# Adafruit_NeoPixel_Ring_16_B.net
KiCad netlist of a schematic drawn in EAGLE
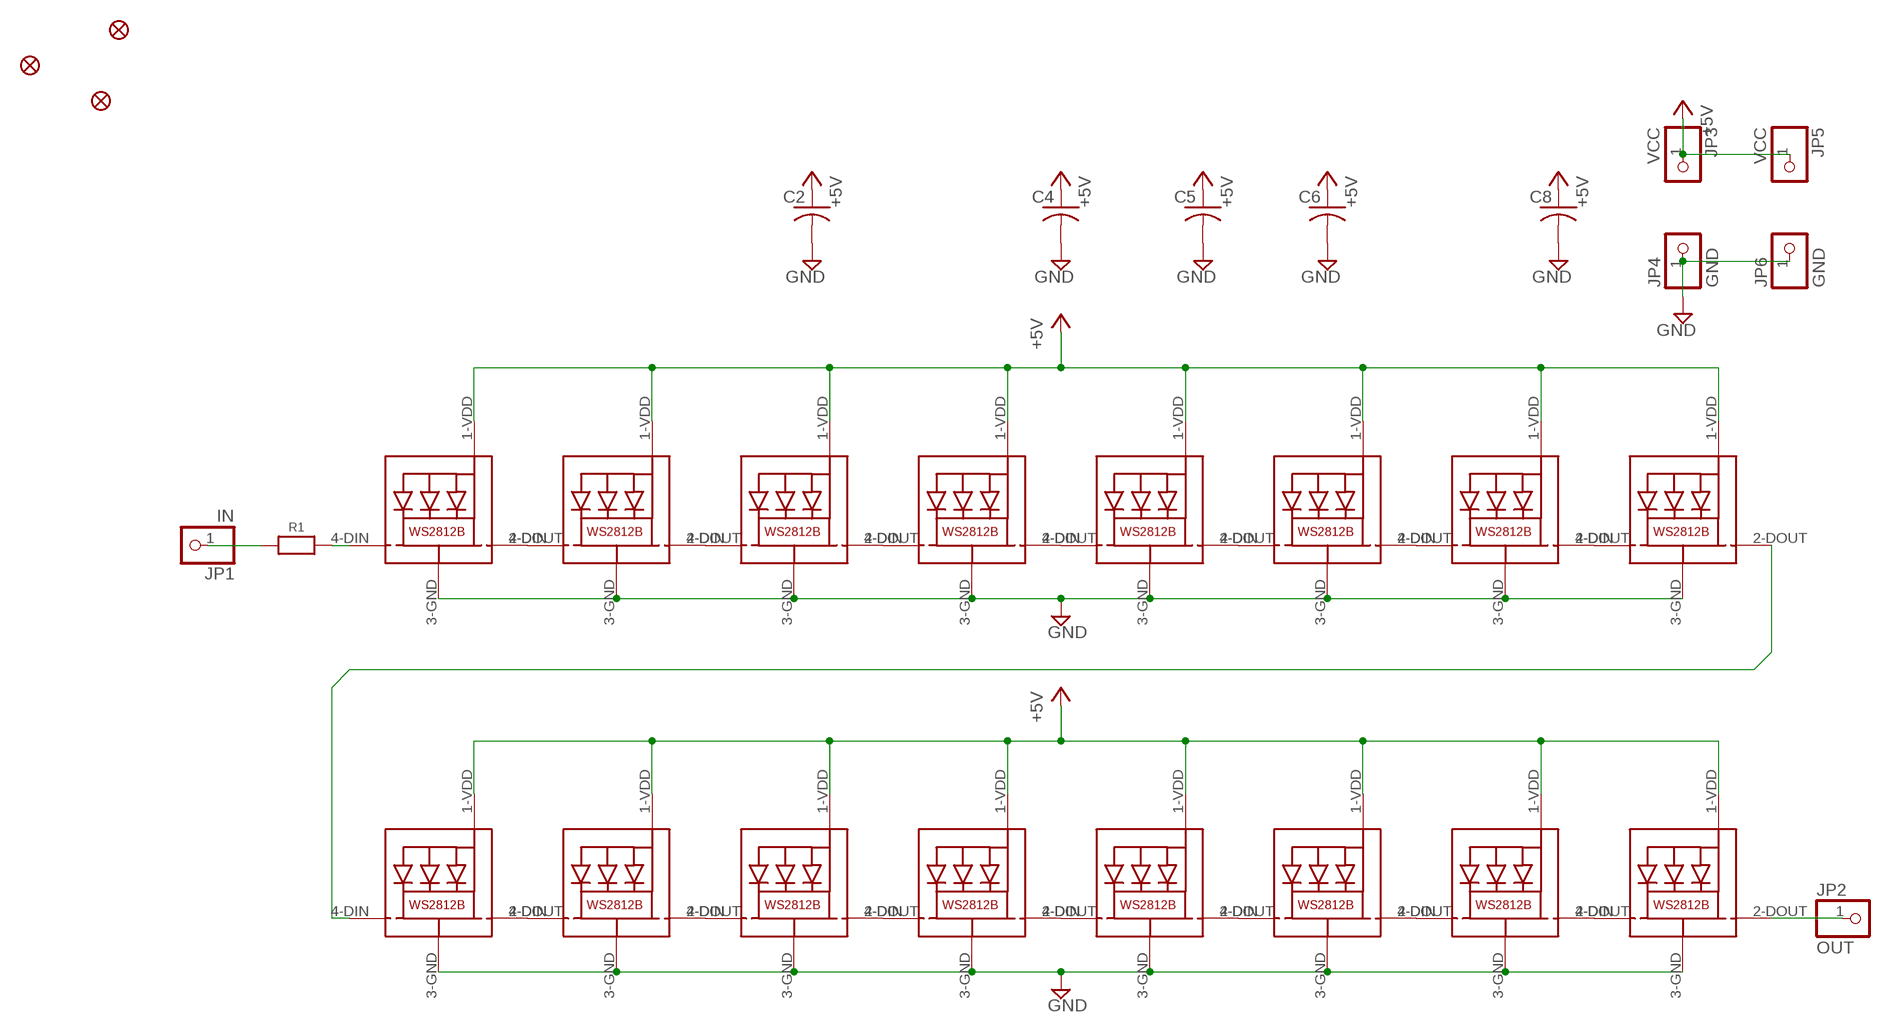
[diagram p0: schematic, sheet 1]

(export (version "E")
  (design (tool "Eeschema 10.0.6"))
  (components
    (comp (ref "C2")
      (value "C-USC0603K")
      (footprint "eagle-import:C0603K")
      (libsource (lib "eagle-import") (part "C-USC0603K"))
    )
    (comp (ref "C4")
      (value "C-USC0603K")
      (footprint "eagle-import:C0603K")
      (libsource (lib "eagle-import") (part "C-USC0603K"))
    )
    (comp (ref "C5")
      (value "C-USC0603K")
      (footprint "eagle-import:C0603K")
      (libsource (lib "eagle-import") (part "C-USC0603K"))
    )
    (comp (ref "C6")
      (value "C-USC0603K")
      (footprint "eagle-import:C0603K")
      (libsource (lib "eagle-import") (part "C-USC0603K"))
    )
    (comp (ref "C8")
      (value "C-USC0603K")
      (footprint "eagle-import:C0603K")
      (libsource (lib "eagle-import") (part "C-USC0603K"))
    )
    (comp (ref "FID1")
      (value "FIDUCIAL\"\"")
      (footprint "eagle-import:FIDUCIAL_1MM")
      (libsource (lib "eagle-import") (part "FIDUCIAL{dblquote}{dblquote}"))
    )
    (comp (ref "FID2")
      (value "FIDUCIAL\"\"")
      (footprint "eagle-import:FIDUCIAL_1MM")
      (libsource (lib "eagle-import") (part "FIDUCIAL{dblquote}{dblquote}"))
    )
    (comp (ref "FID3")
      (value "FIDUCIAL\"\"")
      (footprint "eagle-import:FIDUCIAL_1MM")
      (libsource (lib "eagle-import") (part "FIDUCIAL{dblquote}{dblquote}"))
    )
    (comp (ref "JP1")
      (value "IN")
      (footprint "eagle-import:1X01-CLEANBIG")
      (libsource (lib "eagle-import") (part "PINHD-1X1CB"))
    )
    (comp (ref "JP2")
      (value "OUT")
      (footprint "eagle-import:1X01-CLEANBIG")
      (libsource (lib "eagle-import") (part "PINHD-1X1CB"))
    )
    (comp (ref "JP3")
      (value "VCC")
      (footprint "eagle-import:1X01-CLEANBIG")
      (libsource (lib "eagle-import") (part "PINHD-1X1CB"))
    )
    (comp (ref "JP4")
      (value "GND")
      (footprint "eagle-import:1X01-CLEANBIG")
      (libsource (lib "eagle-import") (part "PINHD-1X1CB"))
    )
    (comp (ref "JP5")
      (value "VCC")
      (footprint "eagle-import:1X01-CLEANBIG")
      (libsource (lib "eagle-import") (part "PINHD-1X1CB"))
    )
    (comp (ref "JP6")
      (value "GND")
      (footprint "eagle-import:1X01-CLEANBIG")
      (libsource (lib "eagle-import") (part "PINHD-1X1CB"))
    )
    (comp (ref "LED1")
      (value "WS2812B5050")
      (footprint "eagle-import:WS2812B")
      (libsource (lib "eagle-import") (part "WS2812B5050"))
    )
    (comp (ref "LED2")
      (value "WS2812B5050")
      (footprint "eagle-import:WS2812B")
      (libsource (lib "eagle-import") (part "WS2812B5050"))
    )
    (comp (ref "LED3")
      (value "WS2812B5050")
      (footprint "eagle-import:WS2812B")
      (libsource (lib "eagle-import") (part "WS2812B5050"))
    )
    (comp (ref "LED4")
      (value "WS2812B5050")
      (footprint "eagle-import:WS2812B")
      (libsource (lib "eagle-import") (part "WS2812B5050"))
    )
    (comp (ref "LED5")
      (value "WS2812B5050")
      (footprint "eagle-import:WS2812B")
      (libsource (lib "eagle-import") (part "WS2812B5050"))
    )
    (comp (ref "LED6")
      (value "WS2812B5050")
      (footprint "eagle-import:WS2812B")
      (libsource (lib "eagle-import") (part "WS2812B5050"))
    )
    (comp (ref "LED7")
      (value "WS2812B5050")
      (footprint "eagle-import:WS2812B")
      (libsource (lib "eagle-import") (part "WS2812B5050"))
    )
    (comp (ref "LED8")
      (value "WS2812B5050")
      (footprint "eagle-import:WS2812B")
      (libsource (lib "eagle-import") (part "WS2812B5050"))
    )
    (comp (ref "LED9")
      (value "WS2812B5050")
      (footprint "eagle-import:WS2812B")
      (libsource (lib "eagle-import") (part "WS2812B5050"))
    )
    (comp (ref "LED10")
      (value "WS2812B5050")
      (footprint "eagle-import:WS2812B")
      (libsource (lib "eagle-import") (part "WS2812B5050"))
    )
    (comp (ref "LED11")
      (value "WS2812B5050")
      (footprint "eagle-import:WS2812B")
      (libsource (lib "eagle-import") (part "WS2812B5050"))
    )
    (comp (ref "LED12")
      (value "WS2812B5050")
      (footprint "eagle-import:WS2812B")
      (libsource (lib "eagle-import") (part "WS2812B5050"))
    )
    (comp (ref "LED13")
      (value "WS2812B5050")
      (footprint "eagle-import:WS2812B")
      (libsource (lib "eagle-import") (part "WS2812B5050"))
    )
    (comp (ref "LED14")
      (value "WS2812B5050")
      (footprint "eagle-import:WS2812B")
      (libsource (lib "eagle-import") (part "WS2812B5050"))
    )
    (comp (ref "LED15")
      (value "WS2812B5050")
      (footprint "eagle-import:WS2812B")
      (libsource (lib "eagle-import") (part "WS2812B5050"))
    )
    (comp (ref "LED16")
      (value "WS2812B5050")
      (footprint "eagle-import:WS2812B")
      (libsource (lib "eagle-import") (part "WS2812B5050"))
    )
    (comp (ref "R1")
      (value "RESISTOR_0603_NOOUT")
      (footprint "eagle-import:0603-NO")
      (libsource (lib "eagle-import") (part "RESISTOR_0603_NOOUT"))
    )
  )
  (nets
    (net (code "1") (name "+5V") (class "Default")
      (node (ref "C2") (pin "1") (pinfunction "1_1") (pintype "passive"))
      (node (ref "C4") (pin "1") (pinfunction "1_1") (pintype "passive"))
      (node (ref "C5") (pin "1") (pinfunction "1_1") (pintype "passive"))
      (node (ref "C6") (pin "1") (pinfunction "1_1") (pintype "passive"))
      (node (ref "C8") (pin "1") (pinfunction "1_1") (pintype "passive"))
      (node (ref "JP3") (pin "1") (pinfunction "1_1") (pintype "passive"))
      (node (ref "JP5") (pin "1") (pinfunction "1_1") (pintype "passive"))
      (node (ref "LED1") (pin "1-VDD") (pinfunction "VDD_1-VDD") (pintype "power_in"))
      (node (ref "LED10") (pin "1-VDD") (pinfunction "VDD_1-VDD") (pintype "power_in"))
      (node (ref "LED11") (pin "1-VDD") (pinfunction "VDD_1-VDD") (pintype "power_in"))
      (node (ref "LED12") (pin "1-VDD") (pinfunction "VDD_1-VDD") (pintype "power_in"))
      (node (ref "LED13") (pin "1-VDD") (pinfunction "VDD_1-VDD") (pintype "power_in"))
      (node (ref "LED14") (pin "1-VDD") (pinfunction "VDD_1-VDD") (pintype "power_in"))
      (node (ref "LED15") (pin "1-VDD") (pinfunction "VDD_1-VDD") (pintype "power_in"))
      (node (ref "LED16") (pin "1-VDD") (pinfunction "VDD_1-VDD") (pintype "power_in"))
      (node (ref "LED2") (pin "1-VDD") (pinfunction "VDD_1-VDD") (pintype "power_in"))
      (node (ref "LED3") (pin "1-VDD") (pinfunction "VDD_1-VDD") (pintype "power_in"))
      (node (ref "LED4") (pin "1-VDD") (pinfunction "VDD_1-VDD") (pintype "power_in"))
      (node (ref "LED5") (pin "1-VDD") (pinfunction "VDD_1-VDD") (pintype "power_in"))
      (node (ref "LED6") (pin "1-VDD") (pinfunction "VDD_1-VDD") (pintype "power_in"))
      (node (ref "LED7") (pin "1-VDD") (pinfunction "VDD_1-VDD") (pintype "power_in"))
      (node (ref "LED8") (pin "1-VDD") (pinfunction "VDD_1-VDD") (pintype "power_in"))
      (node (ref "LED9") (pin "1-VDD") (pinfunction "VDD_1-VDD") (pintype "power_in"))
    )
    (net (code "2") (name "GND") (class "Default")
      (node (ref "C2") (pin "2") (pinfunction "2_2") (pintype "passive"))
      (node (ref "C4") (pin "2") (pinfunction "2_2") (pintype "passive"))
      (node (ref "C5") (pin "2") (pinfunction "2_2") (pintype "passive"))
      (node (ref "C6") (pin "2") (pinfunction "2_2") (pintype "passive"))
      (node (ref "C8") (pin "2") (pinfunction "2_2") (pintype "passive"))
      (node (ref "JP4") (pin "1") (pinfunction "1_1") (pintype "passive"))
      (node (ref "JP6") (pin "1") (pinfunction "1_1") (pintype "passive"))
      (node (ref "LED1") (pin "3-GND") (pinfunction "GND_3-GND") (pintype "power_in"))
      (node (ref "LED10") (pin "3-GND") (pinfunction "GND_3-GND") (pintype "power_in"))
      (node (ref "LED11") (pin "3-GND") (pinfunction "GND_3-GND") (pintype "power_in"))
      (node (ref "LED12") (pin "3-GND") (pinfunction "GND_3-GND") (pintype "power_in"))
      (node (ref "LED13") (pin "3-GND") (pinfunction "GND_3-GND") (pintype "power_in"))
      (node (ref "LED14") (pin "3-GND") (pinfunction "GND_3-GND") (pintype "power_in"))
      (node (ref "LED15") (pin "3-GND") (pinfunction "GND_3-GND") (pintype "power_in"))
      (node (ref "LED16") (pin "3-GND") (pinfunction "GND_3-GND") (pintype "power_in"))
      (node (ref "LED2") (pin "3-GND") (pinfunction "GND_3-GND") (pintype "power_in"))
      (node (ref "LED3") (pin "3-GND") (pinfunction "GND_3-GND") (pintype "power_in"))
      (node (ref "LED4") (pin "3-GND") (pinfunction "GND_3-GND") (pintype "power_in"))
      (node (ref "LED5") (pin "3-GND") (pinfunction "GND_3-GND") (pintype "power_in"))
      (node (ref "LED6") (pin "3-GND") (pinfunction "GND_3-GND") (pintype "power_in"))
      (node (ref "LED7") (pin "3-GND") (pinfunction "GND_3-GND") (pintype "power_in"))
      (node (ref "LED8") (pin "3-GND") (pinfunction "GND_3-GND") (pintype "power_in"))
      (node (ref "LED9") (pin "3-GND") (pinfunction "GND_3-GND") (pintype "power_in"))
    )
    (net (code "3") (name "Net-(JP1-Pad1)") (class "Default")
      (node (ref "JP1") (pin "1") (pinfunction "1_1") (pintype "passive"))
      (node (ref "R1") (pin "1") (pinfunction "1_1") (pintype "passive"))
    )
    (net (code "4") (name "Net-(LED1-DI)") (class "Default")
      (node (ref "LED1") (pin "4-DIN") (pinfunction "DI_4-DIN") (pintype "input"))
      (node (ref "R1") (pin "2") (pinfunction "2_2") (pintype "passive"))
    )
    (net (code "5") (name "Net-(LED1-DO)") (class "Default")
      (node (ref "LED1") (pin "2-DOUT") (pinfunction "DO_2-DOUT") (pintype "output"))
      (node (ref "LED2") (pin "4-DIN") (pinfunction "DI_4-DIN") (pintype "input"))
    )
    (net (code "6") (name "Net-(LED2-DO)") (class "Default")
      (node (ref "LED2") (pin "2-DOUT") (pinfunction "DO_2-DOUT") (pintype "output"))
      (node (ref "LED3") (pin "4-DIN") (pinfunction "DI_4-DIN") (pintype "input"))
    )
    (net (code "7") (name "Net-(LED3-DO)") (class "Default")
      (node (ref "LED3") (pin "2-DOUT") (pinfunction "DO_2-DOUT") (pintype "output"))
      (node (ref "LED4") (pin "4-DIN") (pinfunction "DI_4-DIN") (pintype "input"))
    )
    (net (code "8") (name "Net-(LED4-DO)") (class "Default")
      (node (ref "LED4") (pin "2-DOUT") (pinfunction "DO_2-DOUT") (pintype "output"))
      (node (ref "LED5") (pin "4-DIN") (pinfunction "DI_4-DIN") (pintype "input"))
    )
    (net (code "9") (name "Net-(LED5-DO)") (class "Default")
      (node (ref "LED5") (pin "2-DOUT") (pinfunction "DO_2-DOUT") (pintype "output"))
      (node (ref "LED6") (pin "4-DIN") (pinfunction "DI_4-DIN") (pintype "input"))
    )
    (net (code "10") (name "Net-(LED6-DO)") (class "Default")
      (node (ref "LED6") (pin "2-DOUT") (pinfunction "DO_2-DOUT") (pintype "output"))
      (node (ref "LED7") (pin "4-DIN") (pinfunction "DI_4-DIN") (pintype "input"))
    )
    (net (code "11") (name "Net-(LED7-DO)") (class "Default")
      (node (ref "LED7") (pin "2-DOUT") (pinfunction "DO_2-DOUT") (pintype "output"))
      (node (ref "LED8") (pin "4-DIN") (pinfunction "DI_4-DIN") (pintype "input"))
    )
    (net (code "12") (name "Net-(LED8-DO)") (class "Default")
      (node (ref "LED8") (pin "2-DOUT") (pinfunction "DO_2-DOUT") (pintype "output"))
      (node (ref "LED9") (pin "4-DIN") (pinfunction "DI_4-DIN") (pintype "input"))
    )
    (net (code "13") (name "Net-(LED10-DI)") (class "Default")
      (node (ref "LED10") (pin "4-DIN") (pinfunction "DI_4-DIN") (pintype "input"))
      (node (ref "LED9") (pin "2-DOUT") (pinfunction "DO_2-DOUT") (pintype "output"))
    )
    (net (code "14") (name "Net-(LED10-DO)") (class "Default")
      (node (ref "LED10") (pin "2-DOUT") (pinfunction "DO_2-DOUT") (pintype "output"))
      (node (ref "LED11") (pin "4-DIN") (pinfunction "DI_4-DIN") (pintype "input"))
    )
    (net (code "15") (name "Net-(LED11-DO)") (class "Default")
      (node (ref "LED11") (pin "2-DOUT") (pinfunction "DO_2-DOUT") (pintype "output"))
      (node (ref "LED12") (pin "4-DIN") (pinfunction "DI_4-DIN") (pintype "input"))
    )
    (net (code "16") (name "Net-(LED12-DO)") (class "Default")
      (node (ref "LED12") (pin "2-DOUT") (pinfunction "DO_2-DOUT") (pintype "output"))
      (node (ref "LED13") (pin "4-DIN") (pinfunction "DI_4-DIN") (pintype "input"))
    )
    (net (code "17") (name "Net-(LED13-DO)") (class "Default")
      (node (ref "LED13") (pin "2-DOUT") (pinfunction "DO_2-DOUT") (pintype "output"))
      (node (ref "LED14") (pin "4-DIN") (pinfunction "DI_4-DIN") (pintype "input"))
    )
    (net (code "18") (name "Net-(LED14-DO)") (class "Default")
      (node (ref "LED14") (pin "2-DOUT") (pinfunction "DO_2-DOUT") (pintype "output"))
      (node (ref "LED15") (pin "4-DIN") (pinfunction "DI_4-DIN") (pintype "input"))
    )
    (net (code "19") (name "Net-(LED15-DO)") (class "Default")
      (node (ref "LED15") (pin "2-DOUT") (pinfunction "DO_2-DOUT") (pintype "output"))
      (node (ref "LED16") (pin "4-DIN") (pinfunction "DI_4-DIN") (pintype "input"))
    )
    (net (code "20") (name "Net-(LED16-DO)") (class "Default")
      (node (ref "JP2") (pin "1") (pinfunction "1_1") (pintype "passive"))
      (node (ref "LED16") (pin "2-DOUT") (pinfunction "DO_2-DOUT") (pintype "output"))
    )
  )
)
